# attiny_driver.net
KiCad netlist of a schematic drawn in EAGLE
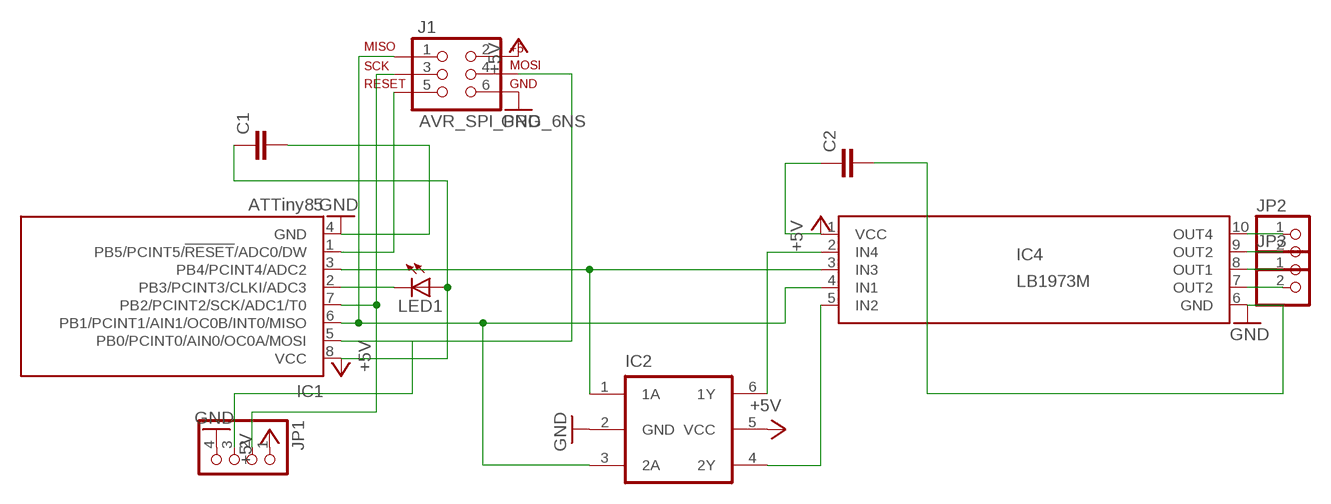
[diagram p0: schematic, sheet 1]

(export (version "E")
  (design (tool "Eeschema 10.0.6"))
  (components
    (comp (ref "C1")
      (value "C-EUC0805")
      (footprint "eagle-import:C0805")
      (libsource (lib "eagle-import") (part "C-EUC0805"))
    )
    (comp (ref "C2")
      (value "C-EUC0805")
      (footprint "eagle-import:C0805")
      (libsource (lib "eagle-import") (part "C-EUC0805"))
    )
    (comp (ref "IC1")
      (value "ATTiny85")
      (footprint "eagle-import:8S2")
      (fields (field (name "MPN") "ATTINY13-20SU"))
      (libsource (lib "eagle-import") (part "TINY13SU-20"))
    )
    (comp (ref "IC2")
      (value "IC_BUFF_SN74LVC2G17DBV")
      (footprint "eagle-import:DBV-R-PDSO-G6")
      (libsource (lib "eagle-import") (part "IC_BUFF_SN74LVC2G17DBV"))
    )
    (comp (ref "IC4")
      (value "LB1973M")
      (footprint "eagle-import:SSOP10")
      (libsource (lib "eagle-import") (part "LB1973M"))
    )
    (comp (ref "J1")
      (value "AVR_SPI_PRG_6NS")
      (footprint "eagle-import:2X3-NS")
      (libsource (lib "eagle-import") (part "AVR_SPI_PRG_6NS"))
    )
    (comp (ref "JP1")
      (value "PINHD-1X4")
      (footprint "eagle-import:1X04")
      (libsource (lib "eagle-import") (part "PINHD-1X4"))
    )
    (comp (ref "JP2")
      (value "PINHD-1X2")
      (footprint "eagle-import:1X02")
      (libsource (lib "eagle-import") (part "PINHD-1X2"))
    )
    (comp (ref "JP3")
      (value "PINHD-1X2")
      (footprint "eagle-import:1X02")
      (libsource (lib "eagle-import") (part "PINHD-1X2"))
    )
    (comp (ref "LED1")
      (value "LED0603")
      (footprint "eagle-import:LED-0603")
      (libsource (lib "eagle-import") (part "LED0603"))
    )
  )
  (nets
    (net (code "1") (name "+5V") (class "Default")
      (node (ref "C1") (pin "1") (pinfunction "1_1") (pintype "passive"))
      (node (ref "C2") (pin "1") (pinfunction "1_1") (pintype "passive"))
      (node (ref "IC1") (pin "8") (pinfunction "VCC_8") (pintype "power_in"))
      (node (ref "IC2") (pin "5") (pinfunction "VCC_5") (pintype "bidirectional"))
      (node (ref "IC4") (pin "1") (pinfunction "VCC_1") (pintype "power_in"))
      (node (ref "J1") (pin "2") (pinfunction "2_2") (pintype "passive"))
      (node (ref "JP1") (pin "1") (pinfunction "1_1") (pintype "passive"))
      (node (ref "LED1") (pin "A") (pinfunction "A_A") (pintype "passive"))
    )
    (net (code "2") (name "GND") (class "Default")
      (node (ref "C1") (pin "2") (pinfunction "2_2") (pintype "passive"))
      (node (ref "C2") (pin "2") (pinfunction "2_2") (pintype "passive"))
      (node (ref "IC1") (pin "4") (pinfunction "GND_4") (pintype "power_in"))
      (node (ref "IC2") (pin "2") (pinfunction "GND_2") (pintype "bidirectional"))
      (node (ref "IC4") (pin "6") (pinfunction "GND_6") (pintype "power_in"))
      (node (ref "J1") (pin "6") (pinfunction "6_6") (pintype "passive"))
      (node (ref "JP1") (pin "4") (pinfunction "4_4") (pintype "passive"))
    )
    (net (code "3") (name "Net-(IC1-PB0{slash}PCINT0{slash}AIN0{slash}OC0A{slash}MOSI)") (class "Default")
      (node (ref "IC1") (pin "5") (pinfunction "PB0/PCINT0/AIN0/OC0A/MOSI_5") (pintype "bidirectional"))
      (node (ref "J1") (pin "4") (pinfunction "4_4") (pintype "passive"))
      (node (ref "JP1") (pin "3") (pinfunction "3_3") (pintype "passive"))
    )
    (net (code "4") (name "Net-(IC1-PB1{slash}PCINT1{slash}AIN1{slash}OC0B{slash}INT0{slash}MISO)") (class "Default")
      (node (ref "IC1") (pin "6") (pinfunction "PB1/PCINT1/AIN1/OC0B/INT0/MISO_6") (pintype "bidirectional"))
      (node (ref "IC2") (pin "3") (pinfunction "2A_3") (pintype "bidirectional"))
      (node (ref "IC4") (pin "4") (pinfunction "IN1_4") (pintype "input"))
      (node (ref "J1") (pin "1") (pinfunction "1_1") (pintype "passive"))
    )
    (net (code "5") (name "Net-(IC1-PB2{slash}PCINT2{slash}SCK{slash}ADC1{slash}T0)") (class "Default")
      (node (ref "IC1") (pin "7") (pinfunction "PB2/PCINT2/SCK/ADC1/T0_7") (pintype "bidirectional"))
      (node (ref "J1") (pin "3") (pinfunction "3_3") (pintype "passive"))
      (node (ref "JP1") (pin "2") (pinfunction "2_2") (pintype "passive"))
    )
    (net (code "6") (name "Net-(IC1-PB3{slash}PCINT3{slash}CLKI{slash}ADC3)") (class "Default")
      (node (ref "IC1") (pin "2") (pinfunction "PB3/PCINT3/CLKI/ADC3_2") (pintype "bidirectional"))
      (node (ref "LED1") (pin "C") (pinfunction "C_C") (pintype "passive"))
    )
    (net (code "7") (name "Net-(IC1-PB4{slash}PCINT4{slash}ADC2)") (class "Default")
      (node (ref "IC1") (pin "3") (pinfunction "PB4/PCINT4/ADC2_3") (pintype "bidirectional"))
      (node (ref "IC2") (pin "1") (pinfunction "1A_1") (pintype "bidirectional"))
      (node (ref "IC4") (pin "3") (pinfunction "IN3_3") (pintype "input"))
    )
    (net (code "8") (name "Net-(IC1-PB5{slash}PCINT5{slash}~{RESET}{slash}ADC0{slash}DW)") (class "Default")
      (node (ref "IC1") (pin "1") (pinfunction "PB5/PCINT5/~{RESET}/ADC0/DW_1") (pintype "bidirectional"))
      (node (ref "J1") (pin "5") (pinfunction "5_5") (pintype "passive"))
    )
    (net (code "9") (name "Net-(IC2-1Y)") (class "Default")
      (node (ref "IC2") (pin "6") (pinfunction "1Y_6") (pintype "bidirectional"))
      (node (ref "IC4") (pin "2") (pinfunction "IN4_2") (pintype "input"))
    )
    (net (code "10") (name "Net-(IC2-2Y)") (class "Default")
      (node (ref "IC2") (pin "4") (pinfunction "2Y_4") (pintype "bidirectional"))
      (node (ref "IC4") (pin "5") (pinfunction "IN2_5") (pintype "input"))
    )
    (net (code "11") (name "Net-(IC4-OUT1)") (class "Default")
      (node (ref "IC4") (pin "8") (pinfunction "OUT1_8") (pintype "output"))
      (node (ref "JP3") (pin "1") (pinfunction "1_1") (pintype "passive"))
    )
    (net (code "12") (name "Net-(IC4-OUT2-Pad7)") (class "Default")
      (node (ref "IC4") (pin "7") (pinfunction "OUT2_7") (pintype "output"))
      (node (ref "JP3") (pin "2") (pinfunction "2_2") (pintype "passive"))
    )
    (net (code "13") (name "Net-(IC4-OUT2-Pad9)") (class "Default")
      (node (ref "IC4") (pin "9") (pinfunction "OUT2_9") (pintype "output"))
      (node (ref "JP2") (pin "2") (pinfunction "2_2") (pintype "passive"))
    )
    (net (code "14") (name "Net-(IC4-OUT4)") (class "Default")
      (node (ref "IC4") (pin "10") (pinfunction "OUT4_10") (pintype "output"))
      (node (ref "JP2") (pin "1") (pinfunction "1_1") (pintype "passive"))
    )
  )
)
